# 7SEGBIG.net
KiCad netlist of a schematic drawn in EAGLE
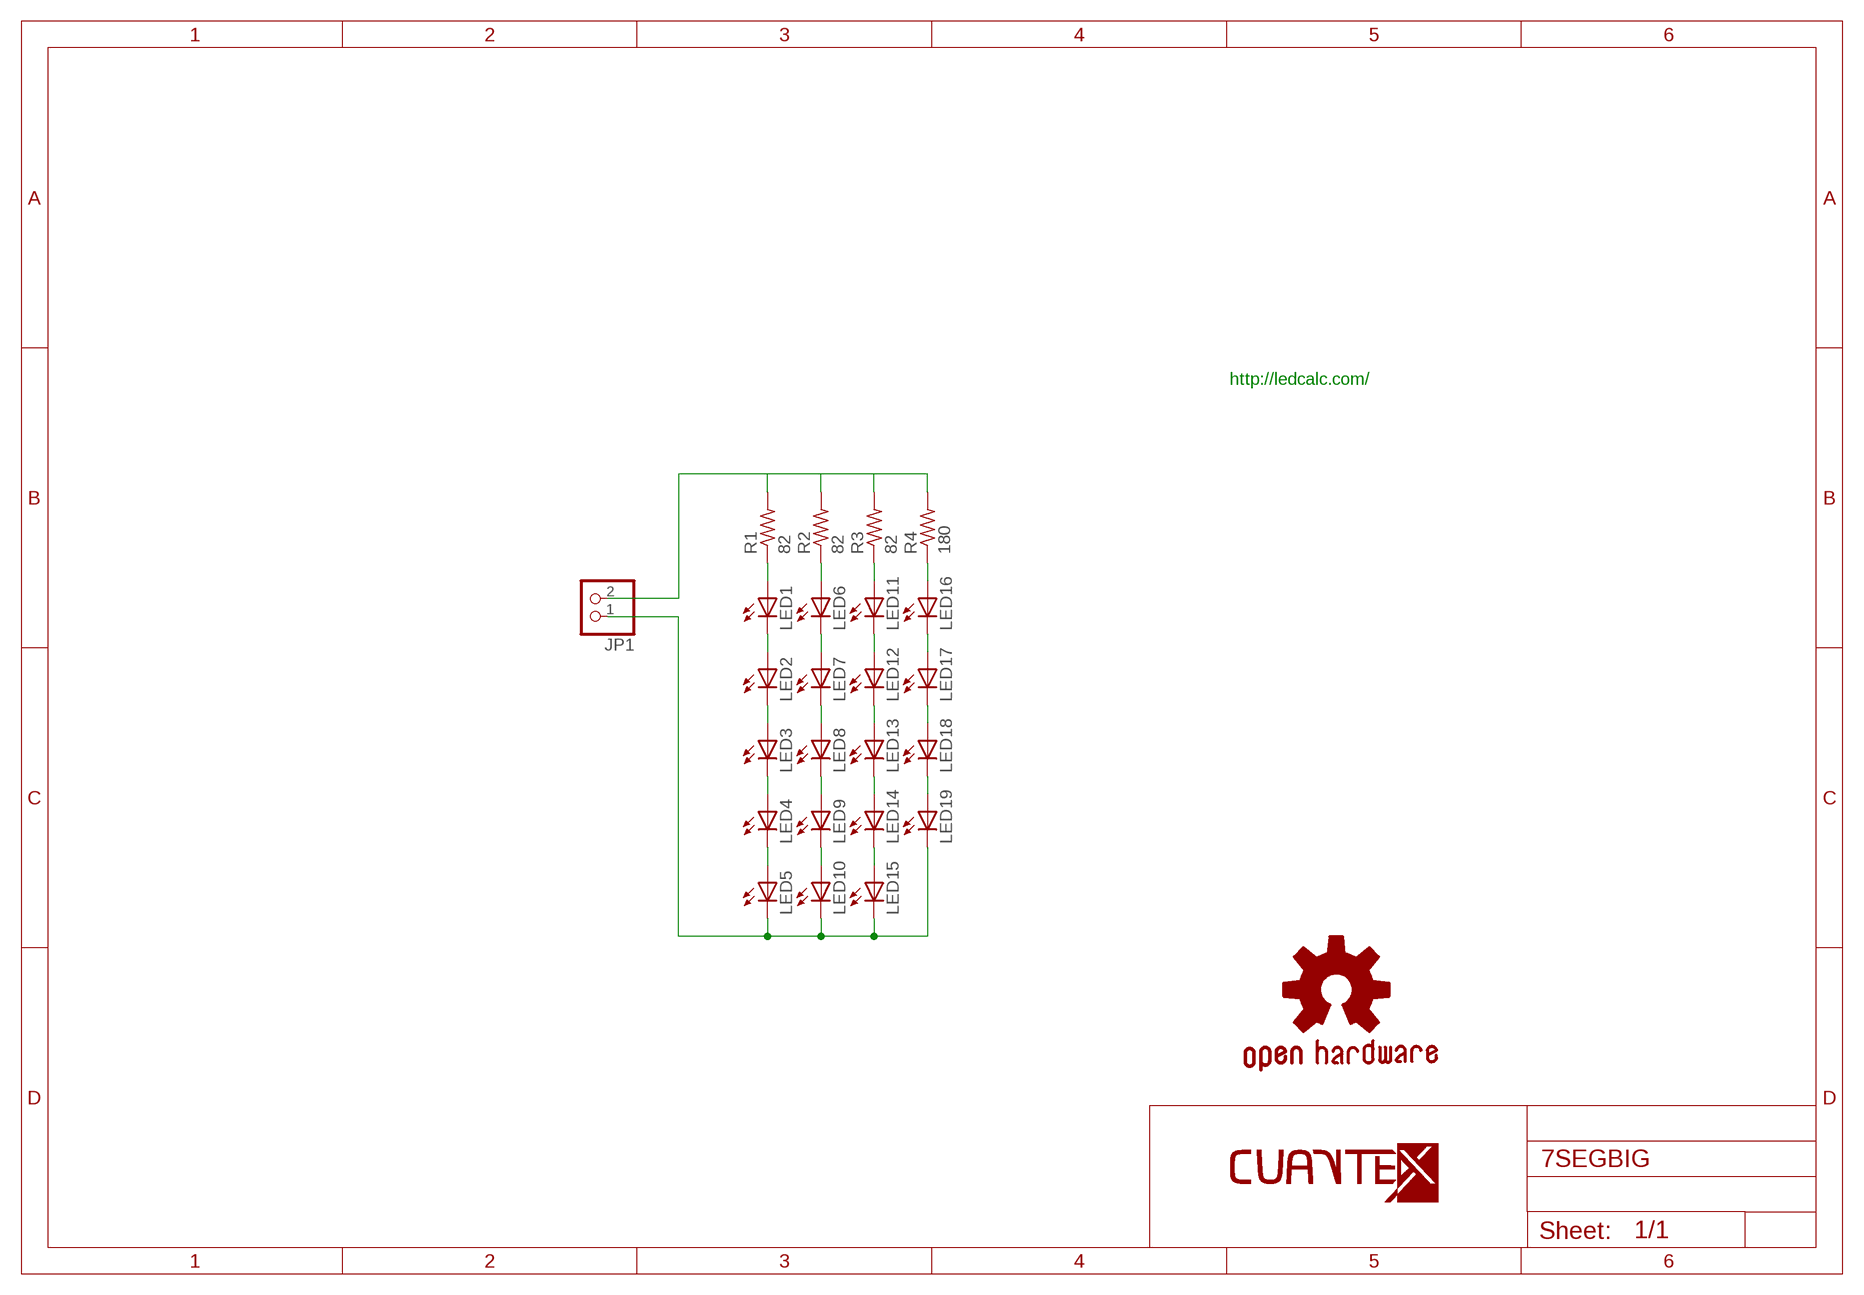
[diagram p0: schematic, sheet 1]

(export (version "E")
  (design (tool "Eeschema 10.0.6"))
  (components
    (comp (ref "GOLD_ORB_SM1")
      (value "OSHWLOGO_GOLD_ORB_LG")
      (footprint "eagle-import:OSHW0")
      (libsource (lib "eagle-import") (part "OSHWLOGO_GOLD_ORB_LG"))
    )
    (comp (ref "JP1")
      (value "PINHD-1X2/90")
      (footprint "eagle-import:1X02_90")
      (libsource (lib "eagle-import") (part "PINHD-1X2/90"))
    )
    (comp (ref "LED1")
      (value "LEDKA-3528ASYC")
      (footprint "eagle-import:KA-3528ASYC")
      (libsource (lib "eagle-import") (part "LEDKA-3528ASYC"))
    )
    (comp (ref "LED2")
      (value "LEDKA-3528ASYC")
      (footprint "eagle-import:KA-3528ASYC")
      (libsource (lib "eagle-import") (part "LEDKA-3528ASYC"))
    )
    (comp (ref "LED3")
      (value "LEDKA-3528ASYC")
      (footprint "eagle-import:KA-3528ASYC")
      (libsource (lib "eagle-import") (part "LEDKA-3528ASYC"))
    )
    (comp (ref "LED4")
      (value "LEDKA-3528ASYC")
      (footprint "eagle-import:KA-3528ASYC")
      (libsource (lib "eagle-import") (part "LEDKA-3528ASYC"))
    )
    (comp (ref "LED5")
      (value "LEDKA-3528ASYC")
      (footprint "eagle-import:KA-3528ASYC")
      (libsource (lib "eagle-import") (part "LEDKA-3528ASYC"))
    )
    (comp (ref "LED6")
      (value "LEDKA-3528ASYC")
      (footprint "eagle-import:KA-3528ASYC")
      (libsource (lib "eagle-import") (part "LEDKA-3528ASYC"))
    )
    (comp (ref "LED7")
      (value "LEDKA-3528ASYC")
      (footprint "eagle-import:KA-3528ASYC")
      (libsource (lib "eagle-import") (part "LEDKA-3528ASYC"))
    )
    (comp (ref "LED8")
      (value "LEDKA-3528ASYC")
      (footprint "eagle-import:KA-3528ASYC")
      (libsource (lib "eagle-import") (part "LEDKA-3528ASYC"))
    )
    (comp (ref "LED9")
      (value "LEDKA-3528ASYC")
      (footprint "eagle-import:KA-3528ASYC")
      (libsource (lib "eagle-import") (part "LEDKA-3528ASYC"))
    )
    (comp (ref "LED10")
      (value "LEDKA-3528ASYC")
      (footprint "eagle-import:KA-3528ASYC")
      (libsource (lib "eagle-import") (part "LEDKA-3528ASYC"))
    )
    (comp (ref "LED11")
      (value "LEDKA-3528ASYC")
      (footprint "eagle-import:KA-3528ASYC")
      (libsource (lib "eagle-import") (part "LEDKA-3528ASYC"))
    )
    (comp (ref "LED12")
      (value "LEDKA-3528ASYC")
      (footprint "eagle-import:KA-3528ASYC")
      (libsource (lib "eagle-import") (part "LEDKA-3528ASYC"))
    )
    (comp (ref "LED13")
      (value "LEDKA-3528ASYC")
      (footprint "eagle-import:KA-3528ASYC")
      (libsource (lib "eagle-import") (part "LEDKA-3528ASYC"))
    )
    (comp (ref "LED14")
      (value "LEDKA-3528ASYC")
      (footprint "eagle-import:KA-3528ASYC")
      (libsource (lib "eagle-import") (part "LEDKA-3528ASYC"))
    )
    (comp (ref "LED15")
      (value "LEDKA-3528ASYC")
      (footprint "eagle-import:KA-3528ASYC")
      (libsource (lib "eagle-import") (part "LEDKA-3528ASYC"))
    )
    (comp (ref "LED16")
      (value "LEDKA-3528ASYC")
      (footprint "eagle-import:KA-3528ASYC")
      (libsource (lib "eagle-import") (part "LEDKA-3528ASYC"))
    )
    (comp (ref "LED17")
      (value "LEDKA-3528ASYC")
      (footprint "eagle-import:KA-3528ASYC")
      (libsource (lib "eagle-import") (part "LEDKA-3528ASYC"))
    )
    (comp (ref "LED18")
      (value "LEDKA-3528ASYC")
      (footprint "eagle-import:KA-3528ASYC")
      (libsource (lib "eagle-import") (part "LEDKA-3528ASYC"))
    )
    (comp (ref "LED19")
      (value "LEDKA-3528ASYC")
      (footprint "eagle-import:KA-3528ASYC")
      (libsource (lib "eagle-import") (part "LEDKA-3528ASYC"))
    )
    (comp (ref "R1")
      (value "82")
      (footprint "eagle-import:R1206")
      (libsource (lib "eagle-import") (part "R-US_R1206"))
    )
    (comp (ref "R2")
      (value "82")
      (footprint "eagle-import:R1206")
      (libsource (lib "eagle-import") (part "R-US_R1206"))
    )
    (comp (ref "R3")
      (value "82")
      (footprint "eagle-import:R1206")
      (libsource (lib "eagle-import") (part "R-US_R1206"))
    )
    (comp (ref "R4")
      (value "180")
      (footprint "eagle-import:R1206")
      (libsource (lib "eagle-import") (part "R-US_R1206"))
    )
    (comp (ref "U$3")
      (value "LOGO-TOP-10MM")
      (footprint "eagle-import:C-000")
      (libsource (lib "eagle-import") (part "LOGO-TOP-10MM"))
    )
  )
  (nets
    (net (code "1") (name "Net-(JP1-Pad1)") (class "Default")
      (node (ref "JP1") (pin "1") (pinfunction "1_1") (pintype "passive"))
      (node (ref "LED10") (pin "C") (pinfunction "C_C") (pintype "passive"))
      (node (ref "LED15") (pin "C") (pinfunction "C_C") (pintype "passive"))
      (node (ref "LED19") (pin "C") (pinfunction "C_C") (pintype "passive"))
      (node (ref "LED5") (pin "C") (pinfunction "C_C") (pintype "passive"))
    )
    (net (code "2") (name "Net-(JP1-Pad2)") (class "Default")
      (node (ref "JP1") (pin "2") (pinfunction "2_2") (pintype "passive"))
      (node (ref "R1") (pin "2") (pinfunction "2_2") (pintype "passive"))
      (node (ref "R2") (pin "2") (pinfunction "2_2") (pintype "passive"))
      (node (ref "R3") (pin "2") (pinfunction "2_2") (pintype "passive"))
      (node (ref "R4") (pin "2") (pinfunction "2_2") (pintype "passive"))
    )
    (net (code "3") (name "Net-(LED1-PadA)") (class "Default")
      (node (ref "LED1") (pin "A") (pinfunction "A_A") (pintype "passive"))
      (node (ref "R1") (pin "1") (pinfunction "1_1") (pintype "passive"))
    )
    (net (code "4") (name "Net-(LED1-PadC)") (class "Default")
      (node (ref "LED1") (pin "C") (pinfunction "C_C") (pintype "passive"))
      (node (ref "LED2") (pin "A") (pinfunction "A_A") (pintype "passive"))
    )
    (net (code "5") (name "Net-(LED2-PadC)") (class "Default")
      (node (ref "LED2") (pin "C") (pinfunction "C_C") (pintype "passive"))
      (node (ref "LED3") (pin "A") (pinfunction "A_A") (pintype "passive"))
    )
    (net (code "6") (name "Net-(LED3-PadC)") (class "Default")
      (node (ref "LED3") (pin "C") (pinfunction "C_C") (pintype "passive"))
      (node (ref "LED4") (pin "A") (pinfunction "A_A") (pintype "passive"))
    )
    (net (code "7") (name "Net-(LED4-PadC)") (class "Default")
      (node (ref "LED4") (pin "C") (pinfunction "C_C") (pintype "passive"))
      (node (ref "LED5") (pin "A") (pinfunction "A_A") (pintype "passive"))
    )
    (net (code "8") (name "Net-(LED6-PadA)") (class "Default")
      (node (ref "LED6") (pin "A") (pinfunction "A_A") (pintype "passive"))
      (node (ref "R2") (pin "1") (pinfunction "1_1") (pintype "passive"))
    )
    (net (code "9") (name "Net-(LED6-PadC)") (class "Default")
      (node (ref "LED6") (pin "C") (pinfunction "C_C") (pintype "passive"))
      (node (ref "LED7") (pin "A") (pinfunction "A_A") (pintype "passive"))
    )
    (net (code "10") (name "Net-(LED7-PadC)") (class "Default")
      (node (ref "LED7") (pin "C") (pinfunction "C_C") (pintype "passive"))
      (node (ref "LED8") (pin "A") (pinfunction "A_A") (pintype "passive"))
    )
    (net (code "11") (name "Net-(LED8-PadC)") (class "Default")
      (node (ref "LED8") (pin "C") (pinfunction "C_C") (pintype "passive"))
      (node (ref "LED9") (pin "A") (pinfunction "A_A") (pintype "passive"))
    )
    (net (code "12") (name "Net-(LED10-PadA)") (class "Default")
      (node (ref "LED10") (pin "A") (pinfunction "A_A") (pintype "passive"))
      (node (ref "LED9") (pin "C") (pinfunction "C_C") (pintype "passive"))
    )
    (net (code "13") (name "Net-(LED11-PadA)") (class "Default")
      (node (ref "LED11") (pin "A") (pinfunction "A_A") (pintype "passive"))
      (node (ref "R3") (pin "1") (pinfunction "1_1") (pintype "passive"))
    )
    (net (code "14") (name "Net-(LED11-PadC)") (class "Default")
      (node (ref "LED11") (pin "C") (pinfunction "C_C") (pintype "passive"))
      (node (ref "LED12") (pin "A") (pinfunction "A_A") (pintype "passive"))
    )
    (net (code "15") (name "Net-(LED12-PadC)") (class "Default")
      (node (ref "LED12") (pin "C") (pinfunction "C_C") (pintype "passive"))
      (node (ref "LED13") (pin "A") (pinfunction "A_A") (pintype "passive"))
    )
    (net (code "16") (name "Net-(LED13-PadC)") (class "Default")
      (node (ref "LED13") (pin "C") (pinfunction "C_C") (pintype "passive"))
      (node (ref "LED14") (pin "A") (pinfunction "A_A") (pintype "passive"))
    )
    (net (code "17") (name "Net-(LED14-PadC)") (class "Default")
      (node (ref "LED14") (pin "C") (pinfunction "C_C") (pintype "passive"))
      (node (ref "LED15") (pin "A") (pinfunction "A_A") (pintype "passive"))
    )
    (net (code "18") (name "Net-(LED16-PadA)") (class "Default")
      (node (ref "LED16") (pin "A") (pinfunction "A_A") (pintype "passive"))
      (node (ref "R4") (pin "1") (pinfunction "1_1") (pintype "passive"))
    )
    (net (code "19") (name "Net-(LED16-PadC)") (class "Default")
      (node (ref "LED16") (pin "C") (pinfunction "C_C") (pintype "passive"))
      (node (ref "LED17") (pin "A") (pinfunction "A_A") (pintype "passive"))
    )
    (net (code "20") (name "Net-(LED17-PadC)") (class "Default")
      (node (ref "LED17") (pin "C") (pinfunction "C_C") (pintype "passive"))
      (node (ref "LED18") (pin "A") (pinfunction "A_A") (pintype "passive"))
    )
    (net (code "21") (name "Net-(LED18-PadC)") (class "Default")
      (node (ref "LED18") (pin "C") (pinfunction "C_C") (pintype "passive"))
      (node (ref "LED19") (pin "A") (pinfunction "A_A") (pintype "passive"))
    )
  )
)
